# motor_driver.net
KiCad netlist of a schematic drawn in EAGLE
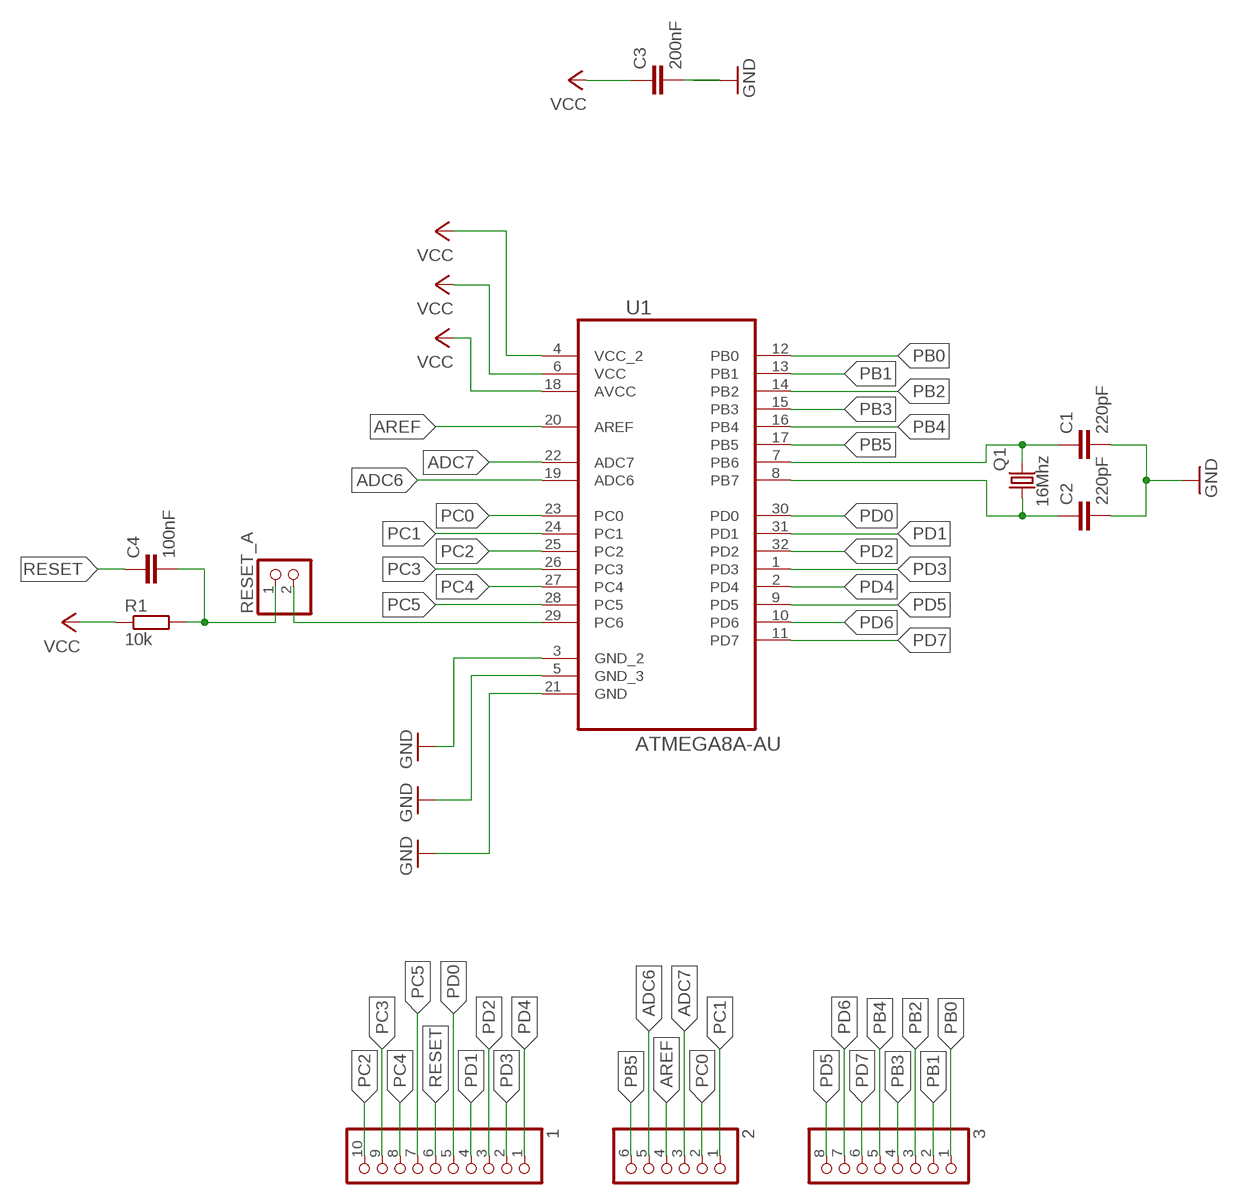
[diagram p0: schematic, sheet 1]

(export (version "E")
  (design (tool "Eeschema 10.0.6"))
  (components
    (comp (ref "1")
      (value "PINHD-1X10")
      (footprint "eagle-import:1X10")
      (libsource (lib "eagle-import") (part "PINHD-1X10"))
    )
    (comp (ref "2")
      (value "PINHD-1X6")
      (footprint "eagle-import:1X06")
      (libsource (lib "eagle-import") (part "PINHD-1X6"))
    )
    (comp (ref "3")
      (value "PINHD-1X8")
      (footprint "eagle-import:1X08")
      (libsource (lib "eagle-import") (part "PINHD-1X8"))
    )
    (comp (ref "C1")
      (value "220pF")
      (footprint "eagle-import:C2.5-3")
      (libsource (lib "eagle-import") (part "C2,5-3"))
    )
    (comp (ref "C2")
      (value "220pF")
      (footprint "eagle-import:C2.5-3")
      (libsource (lib "eagle-import") (part "C2,5-3"))
    )
    (comp (ref "C3")
      (value "200nF")
      (footprint "eagle-import:C2.5-3")
      (libsource (lib "eagle-import") (part "C2,5-3"))
    )
    (comp (ref "C4")
      (value "100nF")
      (footprint "eagle-import:C2.5-3")
      (libsource (lib "eagle-import") (part "C2,5-3"))
    )
    (comp (ref "Q1")
      (value "16Mhz")
      (footprint "eagle-import:HC49U-V")
      (libsource (lib "eagle-import") (part "CRYSTALHC49U-V"))
    )
    (comp (ref "R1")
      (value "10k")
      (footprint "eagle-import:R0805")
      (libsource (lib "eagle-import") (part "R"))
    )
    (comp (ref "RESET_A")
      (value "PINHD-1X2")
      (footprint "eagle-import:1X02")
      (libsource (lib "eagle-import") (part "PINHD-1X2"))
    )
    (comp (ref "U1")
      (value "ATMEGA8A-AU")
      (footprint "eagle-import:QFP80P900X900X120-32N")
      (libsource (lib "eagle-import") (part "ATMEGA8A-AU"))
    )
  )
  (nets
    (net (code "1") (name "ADC6") (class "Default")
      (node (ref "2") (pin "5") (pinfunction "5_5") (pintype "passive"))
      (node (ref "U1") (pin "19") (pinfunction "ADC6_19") (pintype "input"))
    )
    (net (code "2") (name "ADC7") (class "Default")
      (node (ref "2") (pin "3") (pinfunction "3_3") (pintype "passive"))
      (node (ref "U1") (pin "22") (pinfunction "ADC7_22") (pintype "input"))
    )
    (net (code "3") (name "AREF") (class "Default")
      (node (ref "2") (pin "4") (pinfunction "4_4") (pintype "passive"))
      (node (ref "U1") (pin "20") (pinfunction "AREF_20") (pintype "input"))
    )
    (net (code "4") (name "GND") (class "Default")
      (node (ref "C1") (pin "2") (pinfunction "2_2") (pintype "passive"))
      (node (ref "C2") (pin "2") (pinfunction "2_2") (pintype "passive"))
      (node (ref "C3") (pin "2") (pinfunction "2_2") (pintype "passive"))
      (node (ref "U1") (pin "21") (pinfunction "GND_21") (pintype "passive"))
      (node (ref "U1") (pin "3") (pinfunction "GND_2_3") (pintype "passive"))
      (node (ref "U1") (pin "5") (pinfunction "GND_3_5") (pintype "passive"))
    )
    (net (code "5") (name "Net-(C4-Pad2)") (class "Default")
      (node (ref "C4") (pin "2") (pinfunction "2_2") (pintype "passive"))
      (node (ref "R1") (pin "2") (pinfunction "2_2") (pintype "passive"))
      (node (ref "RESET_A") (pin "1") (pinfunction "1_1") (pintype "passive"))
    )
    (net (code "6") (name "Net-(U1-PB6)") (class "Default")
      (node (ref "C1") (pin "1") (pinfunction "1_1") (pintype "passive"))
      (node (ref "Q1") (pin "2") (pinfunction "2_2") (pintype "passive"))
      (node (ref "U1") (pin "7") (pinfunction "PB6_7") (pintype "bidirectional"))
    )
    (net (code "7") (name "Net-(U1-PB7)") (class "Default")
      (node (ref "C2") (pin "1") (pinfunction "1_1") (pintype "passive"))
      (node (ref "Q1") (pin "1") (pinfunction "1_1") (pintype "passive"))
      (node (ref "U1") (pin "8") (pinfunction "PB7_8") (pintype "passive"))
    )
    (net (code "8") (name "Net-(U1-PC6)") (class "Default")
      (node (ref "RESET_A") (pin "2") (pinfunction "2_2") (pintype "passive"))
      (node (ref "U1") (pin "29") (pinfunction "PC6_29") (pintype "bidirectional"))
    )
    (net (code "9") (name "PB0") (class "Default")
      (node (ref "3") (pin "1") (pinfunction "1_1") (pintype "passive"))
      (node (ref "U1") (pin "12") (pinfunction "PB0_12") (pintype "passive"))
    )
    (net (code "10") (name "PB1") (class "Default")
      (node (ref "3") (pin "2") (pinfunction "2_2") (pintype "passive"))
      (node (ref "U1") (pin "13") (pinfunction "PB1_13") (pintype "passive"))
    )
    (net (code "11") (name "PB2") (class "Default")
      (node (ref "3") (pin "3") (pinfunction "3_3") (pintype "passive"))
      (node (ref "U1") (pin "14") (pinfunction "PB2_14") (pintype "passive"))
    )
    (net (code "12") (name "PB3") (class "Default")
      (node (ref "3") (pin "4") (pinfunction "4_4") (pintype "passive"))
      (node (ref "U1") (pin "15") (pinfunction "PB3_15") (pintype "passive"))
    )
    (net (code "13") (name "PB4") (class "Default")
      (node (ref "3") (pin "5") (pinfunction "5_5") (pintype "passive"))
      (node (ref "U1") (pin "16") (pinfunction "PB4_16") (pintype "passive"))
    )
    (net (code "14") (name "PB5") (class "Default")
      (node (ref "2") (pin "6") (pinfunction "6_6") (pintype "passive"))
      (node (ref "U1") (pin "17") (pinfunction "PB5_17") (pintype "passive"))
    )
    (net (code "15") (name "PC0") (class "Default")
      (node (ref "2") (pin "2") (pinfunction "2_2") (pintype "passive"))
      (node (ref "U1") (pin "23") (pinfunction "PC0_23") (pintype "bidirectional"))
    )
    (net (code "16") (name "PC1") (class "Default")
      (node (ref "2") (pin "1") (pinfunction "1_1") (pintype "passive"))
      (node (ref "U1") (pin "24") (pinfunction "PC1_24") (pintype "bidirectional"))
    )
    (net (code "17") (name "PC2") (class "Default")
      (node (ref "1") (pin "10") (pinfunction "10_10") (pintype "passive"))
      (node (ref "U1") (pin "25") (pinfunction "PC2_25") (pintype "bidirectional"))
    )
    (net (code "18") (name "PC3") (class "Default")
      (node (ref "1") (pin "9") (pinfunction "9_9") (pintype "passive"))
      (node (ref "U1") (pin "26") (pinfunction "PC3_26") (pintype "bidirectional"))
    )
    (net (code "19") (name "PC4") (class "Default")
      (node (ref "1") (pin "8") (pinfunction "8_8") (pintype "passive"))
      (node (ref "U1") (pin "27") (pinfunction "PC4_27") (pintype "bidirectional"))
    )
    (net (code "20") (name "PC5") (class "Default")
      (node (ref "1") (pin "7") (pinfunction "7_7") (pintype "passive"))
      (node (ref "U1") (pin "28") (pinfunction "PC5_28") (pintype "bidirectional"))
    )
    (net (code "21") (name "PD0") (class "Default")
      (node (ref "1") (pin "5") (pinfunction "5_5") (pintype "passive"))
      (node (ref "U1") (pin "30") (pinfunction "PD0_30") (pintype "bidirectional"))
    )
    (net (code "22") (name "PD1") (class "Default")
      (node (ref "1") (pin "4") (pinfunction "4_4") (pintype "passive"))
      (node (ref "U1") (pin "31") (pinfunction "PD1_31") (pintype "bidirectional"))
    )
    (net (code "23") (name "PD2") (class "Default")
      (node (ref "1") (pin "3") (pinfunction "3_3") (pintype "passive"))
      (node (ref "U1") (pin "32") (pinfunction "PD2_32") (pintype "bidirectional"))
    )
    (net (code "24") (name "PD3") (class "Default")
      (node (ref "1") (pin "2") (pinfunction "2_2") (pintype "passive"))
      (node (ref "U1") (pin "1") (pinfunction "PD3_1") (pintype "bidirectional"))
    )
    (net (code "25") (name "PD4") (class "Default")
      (node (ref "1") (pin "1") (pinfunction "1_1") (pintype "passive"))
      (node (ref "U1") (pin "2") (pinfunction "PD4_2") (pintype "bidirectional"))
    )
    (net (code "26") (name "PD5") (class "Default")
      (node (ref "3") (pin "8") (pinfunction "8_8") (pintype "passive"))
      (node (ref "U1") (pin "9") (pinfunction "PD5_9") (pintype "passive"))
    )
    (net (code "27") (name "PD6") (class "Default")
      (node (ref "3") (pin "7") (pinfunction "7_7") (pintype "passive"))
      (node (ref "U1") (pin "10") (pinfunction "PD6_10") (pintype "passive"))
    )
    (net (code "28") (name "PD7") (class "Default")
      (node (ref "3") (pin "6") (pinfunction "6_6") (pintype "passive"))
      (node (ref "U1") (pin "11") (pinfunction "PD7_11") (pintype "passive"))
    )
    (net (code "29") (name "RESET") (class "Default")
      (node (ref "1") (pin "6") (pinfunction "6_6") (pintype "passive"))
      (node (ref "C4") (pin "1") (pinfunction "1_1") (pintype "passive"))
    )
    (net (code "30") (name "VCC") (class "Default")
      (node (ref "C3") (pin "1") (pinfunction "1_1") (pintype "passive"))
      (node (ref "R1") (pin "1") (pinfunction "1_1") (pintype "passive"))
      (node (ref "U1") (pin "18") (pinfunction "AVCC_18") (pintype "power_in"))
      (node (ref "U1") (pin "4") (pinfunction "VCC_2_4") (pintype "power_in"))
      (node (ref "U1") (pin "6") (pinfunction "VCC_6") (pintype "power_in"))
    )
  )
)
